# ram.net
KiCad netlist of a schematic drawn in Altium Designer
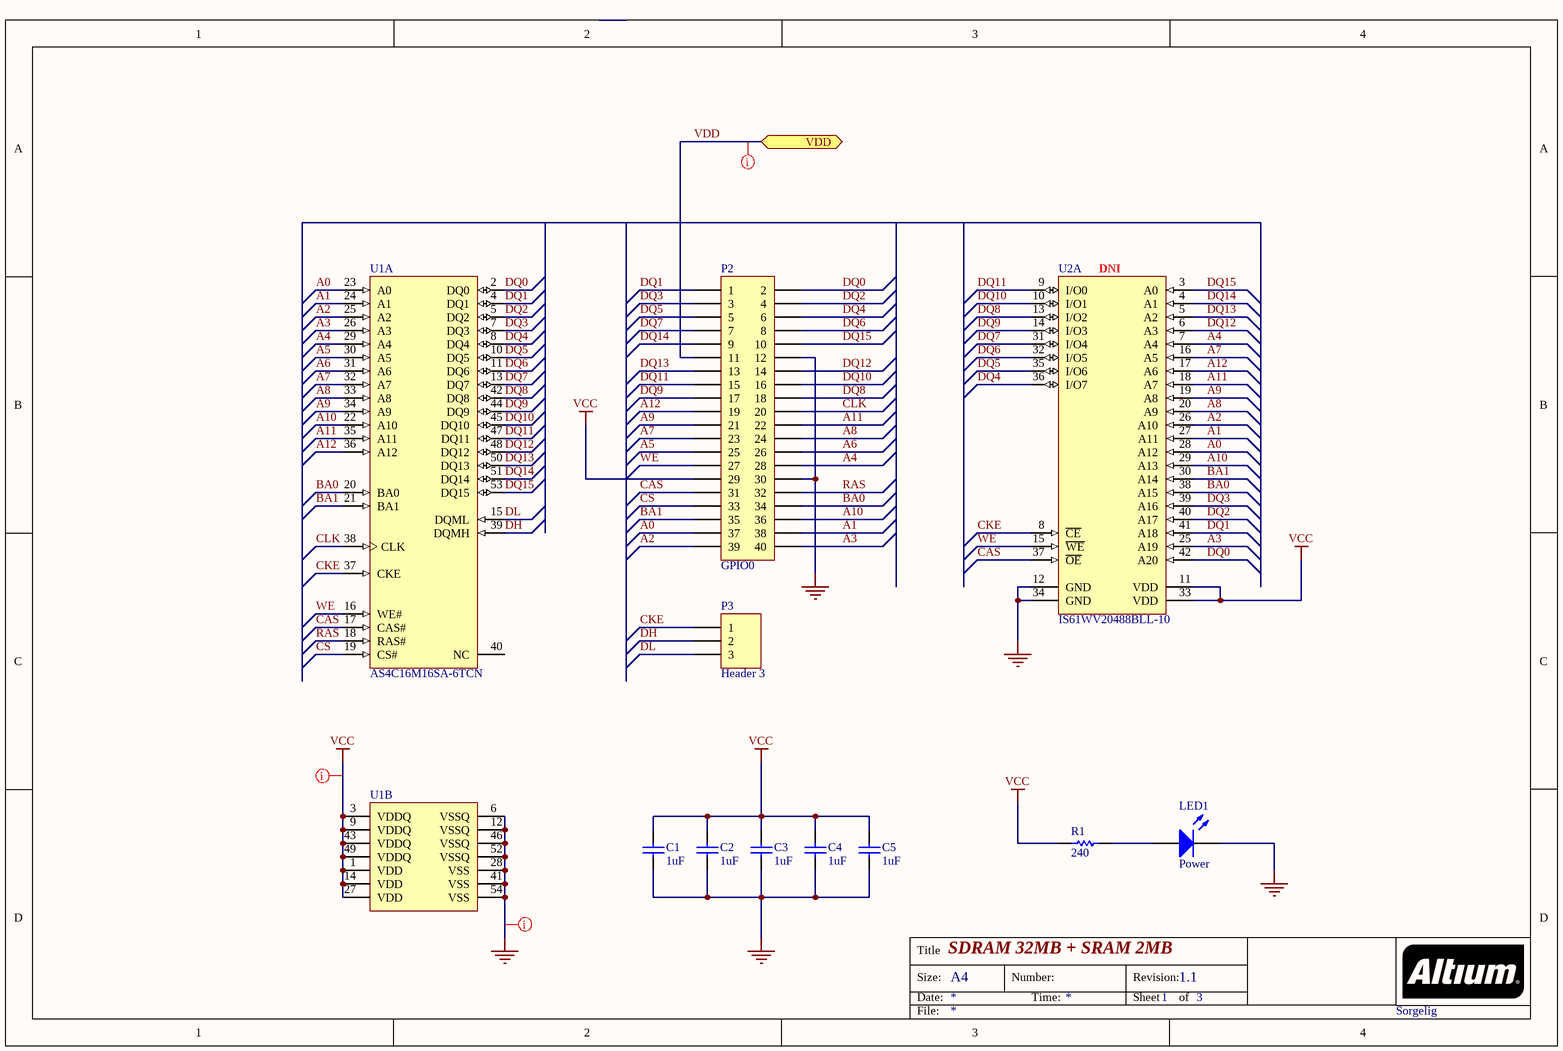
[diagram p0: ram.SchDoc]

(export (version "E")
  (design (tool "Eeschema 10.0.6"))
  (components
    (comp (ref "C1")
      (value "1uF")
      (footprint "C0805")
      (description "Ceramic Chip Capacitor - Standard")
      (fields (field (name "Comment") "C0805") (field (name "PUBLISHER") "Altium Limited"))
      (libsource (lib "lib") (part "C0805"))
    )
    (comp (ref "C2")
      (value "1uF")
      (footprint "C0805")
      (description "Ceramic Chip Capacitor - Standard")
      (fields (field (name "Comment") "C0805") (field (name "PUBLISHER") "Altium Limited"))
      (libsource (lib "lib") (part "C0805"))
    )
    (comp (ref "C3")
      (value "1uF")
      (footprint "C0805")
      (description "Ceramic Chip Capacitor - Standard")
      (fields (field (name "Comment") "+") (field (name "PUBLISHER") "Altium Limited"))
      (libsource (lib "lib") (part "C0805"))
    )
    (comp (ref "C4")
      (value "1uF")
      (footprint "C0805")
      (description "Ceramic Chip Capacitor - Standard")
      (fields (field (name "Comment") "C0805") (field (name "PUBLISHER") "Altium Limited"))
      (libsource (lib "lib") (part "C0805"))
    )
    (comp (ref "C5")
      (value "1uF")
      (footprint "C0805")
      (description "Ceramic Chip Capacitor - Standard")
      (fields (field (name "Comment") "+") (field (name "PUBLISHER") "Altium Limited"))
      (libsource (lib "lib") (part "C0805"))
    )
    (comp (ref "LED1")
      (value "Power")
      (footprint "LEDB0805")
      (description "Typical RED, GREEN, YELLOW, AMBER GaAs LED")
      (fields (field (name "PUBLISHER") "Altium Limited"))
      (libsource (lib "Miscellaneous Devices") (part "LED2"))
    )
    (comp (ref "P2")
      (value "GPIO0")
      (footprint "HDR20x2")
      (description "Header, 20-Pin, Dual row")
      (fields (field (name "PUBLISHER") "Altium Limited"))
      (libsource (lib "Miscellaneous Connectors") (part "Header 20X2"))
    )
    (comp (ref "P3")
      (value "Header 3")
      (footprint "HDR1X3")
      (description "Header, 3-Pin")
      (fields (field (name "PUBLISHER") "Altium Limited"))
      (libsource (lib "Miscellaneous Connectors") (part "Header 3"))
    )
    (comp (ref "R1")
      (value "240")
      (footprint "R0805")
      (fields (field (name "PUBLISHER") "Altium Limited"))
      (libsource (lib "lib") (part "R0805"))
    )
    (comp (ref "U1")
      (value "AS4C16M16SA-6TCN")
      (footprint "TSOP54")
      (description "256Mb SDR SDRAM, 16Mb x 16, 6ns, 3.3V, 54-Pin TSOP")
      (fields (field (name "VOLTAGE") "3.3V ") (field (name "MANUFACTURER") "Micron"))
      (libsource (lib "lib") (part "AS4C16M16SA-6TCN"))
    )
    (comp (ref "U2")
      (value "IS61WV20488BLL-10")
      (footprint "ISSI-TSOP-2-44_N")
      (description "16 M High Speed CMOS SRAM, 2 M x 8, -40 to 85 degC, 44-Pin SOP (TSOP-2-44)")
      (fields
        (field (name "MANUFACTURER") "Integrated Silicon Solution Inc (ISSI)")
        (field (name "PARTNUMBER") "IS61WV20488BLL-10TI")
      )
      (libsource (lib "lib") (part "IS61WV20488BLL-10TI"))
    )
  )
  (nets
    (net (code "1") (name "/A0") (class "Default")
      (node (ref "P2") (pin "37") (pinfunction "37_37") (pintype "passive"))
      (node (ref "U1") (pin "23") (pinfunction "A0_23") (pintype "input"))
      (node (ref "U2") (pin "28") (pinfunction "A12_28") (pintype "input"))
    )
    (net (code "2") (name "/A1") (class "Default")
      (node (ref "P2") (pin "38") (pinfunction "38_38") (pintype "passive"))
      (node (ref "U1") (pin "24") (pinfunction "A1_24") (pintype "input"))
      (node (ref "U2") (pin "27") (pinfunction "A11_27") (pintype "input"))
    )
    (net (code "3") (name "/A2") (class "Default")
      (node (ref "P2") (pin "39") (pinfunction "39_39") (pintype "passive"))
      (node (ref "U1") (pin "25") (pinfunction "A2_25") (pintype "input"))
      (node (ref "U2") (pin "26") (pinfunction "A10_26") (pintype "input"))
    )
    (net (code "4") (name "/A3") (class "Default")
      (node (ref "P2") (pin "40") (pinfunction "40_40") (pintype "passive"))
      (node (ref "U1") (pin "26") (pinfunction "A3_26") (pintype "input"))
      (node (ref "U2") (pin "25") (pinfunction "A19_25") (pintype "input"))
    )
    (net (code "5") (name "/A4") (class "Default")
      (node (ref "P2") (pin "28") (pinfunction "28_28") (pintype "passive"))
      (node (ref "U1") (pin "29") (pinfunction "A4_29") (pintype "input"))
      (node (ref "U2") (pin "7") (pinfunction "A4_7") (pintype "input"))
    )
    (net (code "6") (name "/A5") (class "Default")
      (node (ref "P2") (pin "25") (pinfunction "25_25") (pintype "passive"))
      (node (ref "U1") (pin "30") (pinfunction "A5_30") (pintype "input"))
    )
    (net (code "7") (name "/A6") (class "Default")
      (node (ref "P2") (pin "26") (pinfunction "26_26") (pintype "passive"))
      (node (ref "U1") (pin "31") (pinfunction "A6_31") (pintype "input"))
    )
    (net (code "8") (name "/A7") (class "Default")
      (node (ref "P2") (pin "23") (pinfunction "23_23") (pintype "passive"))
      (node (ref "U1") (pin "32") (pinfunction "A7_32") (pintype "input"))
      (node (ref "U2") (pin "16") (pinfunction "A5_16") (pintype "input"))
    )
    (net (code "9") (name "/A8") (class "Default")
      (node (ref "P2") (pin "24") (pinfunction "24_24") (pintype "passive"))
      (node (ref "U1") (pin "33") (pinfunction "A8_33") (pintype "input"))
      (node (ref "U2") (pin "20") (pinfunction "A9_20") (pintype "input"))
    )
    (net (code "10") (name "/A9") (class "Default")
      (node (ref "P2") (pin "21") (pinfunction "21_21") (pintype "passive"))
      (node (ref "U1") (pin "34") (pinfunction "A9_34") (pintype "input"))
      (node (ref "U2") (pin "19") (pinfunction "A8_19") (pintype "input"))
    )
    (net (code "11") (name "/A10") (class "Default")
      (node (ref "P2") (pin "36") (pinfunction "36_36") (pintype "passive"))
      (node (ref "U1") (pin "22") (pinfunction "A10_22") (pintype "input"))
      (node (ref "U2") (pin "29") (pinfunction "A13_29") (pintype "input"))
    )
    (net (code "12") (name "/A11") (class "Default")
      (node (ref "P2") (pin "22") (pinfunction "22_22") (pintype "passive"))
      (node (ref "U1") (pin "35") (pinfunction "A11_35") (pintype "input"))
      (node (ref "U2") (pin "18") (pinfunction "A7_18") (pintype "input"))
    )
    (net (code "13") (name "/A12") (class "Default")
      (node (ref "P2") (pin "19") (pinfunction "19_19") (pintype "passive"))
      (node (ref "U1") (pin "36") (pinfunction "A12_36") (pintype "input"))
      (node (ref "U2") (pin "17") (pinfunction "A6_17") (pintype "input"))
    )
    (net (code "14") (name "/BA0") (class "Default")
      (node (ref "P2") (pin "34") (pinfunction "34_34") (pintype "passive"))
      (node (ref "U1") (pin "20") (pinfunction "BA0_20") (pintype "input"))
      (node (ref "U2") (pin "38") (pinfunction "A15_38") (pintype "input"))
    )
    (net (code "15") (name "/BA1") (class "Default")
      (node (ref "P2") (pin "35") (pinfunction "35_35") (pintype "passive"))
      (node (ref "U1") (pin "21") (pinfunction "BA1_21") (pintype "input"))
      (node (ref "U2") (pin "30") (pinfunction "A14_30") (pintype "input"))
    )
    (net (code "16") (name "/CAS") (class "Default")
      (node (ref "P2") (pin "31") (pinfunction "31_31") (pintype "passive"))
      (node (ref "U1") (pin "17") (pinfunction "CAS#_17") (pintype "input"))
      (node (ref "U2") (pin "37") (pinfunction "~{OE}_37") (pintype "input"))
    )
    (net (code "17") (name "/CKE") (class "Default")
      (node (ref "P3") (pin "1") (pinfunction "1_1") (pintype "passive"))
      (node (ref "U1") (pin "37") (pinfunction "CKE_37") (pintype "input"))
      (node (ref "U2") (pin "8") (pinfunction "~{CE}_8") (pintype "input"))
    )
    (net (code "18") (name "/CLK") (class "Default")
      (node (ref "P2") (pin "20") (pinfunction "20_20") (pintype "passive"))
      (node (ref "U1") (pin "38") (pinfunction "CLK_38") (pintype "input"))
    )
    (net (code "19") (name "/CS") (class "Default")
      (node (ref "P2") (pin "33") (pinfunction "33_33") (pintype "passive"))
      (node (ref "U1") (pin "19") (pinfunction "CS#_19") (pintype "input"))
    )
    (net (code "20") (name "/DH") (class "Default")
      (node (ref "P3") (pin "2") (pinfunction "2_2") (pintype "passive"))
      (node (ref "U1") (pin "39") (pinfunction "DQMH_39") (pintype "input"))
    )
    (net (code "21") (name "/DL") (class "Default")
      (node (ref "P3") (pin "3") (pinfunction "3_3") (pintype "passive"))
      (node (ref "U1") (pin "15") (pinfunction "DQML_15") (pintype "input"))
    )
    (net (code "22") (name "/DQ0") (class "Default")
      (node (ref "P2") (pin "2") (pinfunction "2_2") (pintype "passive"))
      (node (ref "U1") (pin "2") (pinfunction "DQ0_2") (pintype "bidirectional"))
      (node (ref "U2") (pin "42") (pinfunction "A20_42") (pintype "input"))
    )
    (net (code "23") (name "/DQ1") (class "Default")
      (node (ref "P2") (pin "1") (pinfunction "1_1") (pintype "passive"))
      (node (ref "U1") (pin "4") (pinfunction "DQ1_4") (pintype "bidirectional"))
      (node (ref "U2") (pin "41") (pinfunction "A18_41") (pintype "input"))
    )
    (net (code "24") (name "/DQ2") (class "Default")
      (node (ref "P2") (pin "4") (pinfunction "4_4") (pintype "passive"))
      (node (ref "U1") (pin "5") (pinfunction "DQ2_5") (pintype "bidirectional"))
      (node (ref "U2") (pin "40") (pinfunction "A17_40") (pintype "input"))
    )
    (net (code "25") (name "/DQ3") (class "Default")
      (node (ref "P2") (pin "3") (pinfunction "3_3") (pintype "passive"))
      (node (ref "U1") (pin "7") (pinfunction "DQ3_7") (pintype "bidirectional"))
      (node (ref "U2") (pin "39") (pinfunction "A16_39") (pintype "input"))
    )
    (net (code "26") (name "/DQ4") (class "Default")
      (node (ref "P2") (pin "6") (pinfunction "6_6") (pintype "passive"))
      (node (ref "U1") (pin "8") (pinfunction "DQ4_8") (pintype "bidirectional"))
      (node (ref "U2") (pin "36") (pinfunction "I/O7_36") (pintype "bidirectional"))
    )
    (net (code "27") (name "/DQ5") (class "Default")
      (node (ref "P2") (pin "5") (pinfunction "5_5") (pintype "passive"))
      (node (ref "U1") (pin "10") (pinfunction "DQ5_10") (pintype "bidirectional"))
      (node (ref "U2") (pin "35") (pinfunction "I/O6_35") (pintype "bidirectional"))
    )
    (net (code "28") (name "/DQ6") (class "Default")
      (node (ref "P2") (pin "8") (pinfunction "8_8") (pintype "passive"))
      (node (ref "U1") (pin "11") (pinfunction "DQ6_11") (pintype "bidirectional"))
      (node (ref "U2") (pin "32") (pinfunction "I/O5_32") (pintype "bidirectional"))
    )
    (net (code "29") (name "/DQ7") (class "Default")
      (node (ref "P2") (pin "7") (pinfunction "7_7") (pintype "passive"))
      (node (ref "U1") (pin "13") (pinfunction "DQ7_13") (pintype "bidirectional"))
      (node (ref "U2") (pin "31") (pinfunction "I/O4_31") (pintype "bidirectional"))
    )
    (net (code "30") (name "/DQ8") (class "Default")
      (node (ref "P2") (pin "18") (pinfunction "18_18") (pintype "passive"))
      (node (ref "U1") (pin "42") (pinfunction "DQ8_42") (pintype "bidirectional"))
      (node (ref "U2") (pin "13") (pinfunction "I/O2_13") (pintype "bidirectional"))
    )
    (net (code "31") (name "/DQ9") (class "Default")
      (node (ref "P2") (pin "17") (pinfunction "17_17") (pintype "passive"))
      (node (ref "U1") (pin "44") (pinfunction "DQ9_44") (pintype "bidirectional"))
      (node (ref "U2") (pin "14") (pinfunction "I/O3_14") (pintype "bidirectional"))
    )
    (net (code "32") (name "/DQ10") (class "Default")
      (node (ref "P2") (pin "16") (pinfunction "16_16") (pintype "passive"))
      (node (ref "U1") (pin "45") (pinfunction "DQ10_45") (pintype "bidirectional"))
      (node (ref "U2") (pin "10") (pinfunction "I/O1_10") (pintype "bidirectional"))
    )
    (net (code "33") (name "/DQ11") (class "Default")
      (node (ref "P2") (pin "15") (pinfunction "15_15") (pintype "passive"))
      (node (ref "U1") (pin "47") (pinfunction "DQ11_47") (pintype "bidirectional"))
      (node (ref "U2") (pin "9") (pinfunction "I/O0_9") (pintype "bidirectional"))
    )
    (net (code "34") (name "/DQ12") (class "Default")
      (node (ref "P2") (pin "14") (pinfunction "14_14") (pintype "passive"))
      (node (ref "U1") (pin "48") (pinfunction "DQ12_48") (pintype "bidirectional"))
      (node (ref "U2") (pin "6") (pinfunction "A3_6") (pintype "input"))
    )
    (net (code "35") (name "/DQ13") (class "Default")
      (node (ref "P2") (pin "13") (pinfunction "13_13") (pintype "passive"))
      (node (ref "U1") (pin "50") (pinfunction "DQ13_50") (pintype "bidirectional"))
      (node (ref "U2") (pin "5") (pinfunction "A2_5") (pintype "input"))
    )
    (net (code "36") (name "/DQ14") (class "Default")
      (node (ref "P2") (pin "9") (pinfunction "9_9") (pintype "passive"))
      (node (ref "U1") (pin "51") (pinfunction "DQ14_51") (pintype "bidirectional"))
      (node (ref "U2") (pin "4") (pinfunction "A1_4") (pintype "input"))
    )
    (net (code "37") (name "/DQ15") (class "Default")
      (node (ref "P2") (pin "10") (pinfunction "10_10") (pintype "passive"))
      (node (ref "U1") (pin "53") (pinfunction "DQ15_53") (pintype "bidirectional"))
      (node (ref "U2") (pin "3") (pinfunction "A0_3") (pintype "input"))
    )
    (net (code "38") (name "/RAS") (class "Default")
      (node (ref "P2") (pin "32") (pinfunction "32_32") (pintype "passive"))
      (node (ref "U1") (pin "18") (pinfunction "RAS#_18") (pintype "input"))
    )
    (net (code "39") (name "/VDD") (class "Default")
      (node (ref "P2") (pin "11") (pinfunction "11_11") (pintype "power_in"))
    )
    (net (code "40") (name "/WE") (class "Default")
      (node (ref "P2") (pin "27") (pinfunction "27_27") (pintype "passive"))
      (node (ref "U1") (pin "16") (pinfunction "WE#_16") (pintype "input"))
      (node (ref "U2") (pin "15") (pinfunction "~{WE}_15") (pintype "input"))
    )
    (net (code "41") (name "GND") (class "Default")
      (node (ref "C1") (pin "1") (pinfunction "1_1") (pintype "passive"))
      (node (ref "C2") (pin "1") (pinfunction "1_1") (pintype "passive"))
      (node (ref "C3") (pin "1") (pinfunction "1_1") (pintype "passive"))
      (node (ref "C4") (pin "1") (pinfunction "1_1") (pintype "passive"))
      (node (ref "C5") (pin "1") (pinfunction "1_1") (pintype "passive"))
      (node (ref "LED1") (pin "2") (pinfunction "K_2") (pintype "passive"))
      (node (ref "P2") (pin "12") (pinfunction "12_12") (pintype "power_in"))
      (node (ref "P2") (pin "30") (pinfunction "30_30") (pintype "power_in"))
      (node (ref "U1") (pin "12") (pinfunction "VSSQ_12") (pintype "power_in"))
      (node (ref "U1") (pin "28") (pinfunction "VSS_28") (pintype "power_in"))
      (node (ref "U1") (pin "41") (pinfunction "VSS_41") (pintype "power_in"))
      (node (ref "U1") (pin "46") (pinfunction "VSSQ_46") (pintype "power_in"))
      (node (ref "U1") (pin "52") (pinfunction "VSSQ_52") (pintype "power_in"))
      (node (ref "U1") (pin "54") (pinfunction "VSS_54") (pintype "power_in"))
      (node (ref "U1") (pin "6") (pinfunction "VSSQ_6") (pintype "power_in"))
      (node (ref "U2") (pin "12") (pinfunction "GND_12") (pintype "power_in"))
      (node (ref "U2") (pin "34") (pinfunction "GND_34") (pintype "power_in"))
    )
    (net (code "42") (name "Net-(LED1-A)") (class "Default")
      (node (ref "LED1") (pin "1") (pinfunction "A_1") (pintype "passive"))
      (node (ref "R1") (pin "1") (pinfunction "1_1") (pintype "passive"))
    )
    (net (code "43") (name "VCC") (class "Default")
      (node (ref "C1") (pin "2") (pinfunction "2_2") (pintype "passive"))
      (node (ref "C2") (pin "2") (pinfunction "2_2") (pintype "passive"))
      (node (ref "C3") (pin "2") (pinfunction "2_2") (pintype "passive"))
      (node (ref "C4") (pin "2") (pinfunction "2_2") (pintype "passive"))
      (node (ref "C5") (pin "2") (pinfunction "2_2") (pintype "passive"))
      (node (ref "P2") (pin "29") (pinfunction "29_29") (pintype "power_in"))
      (node (ref "R1") (pin "2") (pinfunction "2_2") (pintype "passive"))
      (node (ref "U1") (pin "1") (pinfunction "VDD_1") (pintype "power_in"))
      (node (ref "U1") (pin "14") (pinfunction "VDD_14") (pintype "power_in"))
      (node (ref "U1") (pin "27") (pinfunction "VDD_27") (pintype "power_in"))
      (node (ref "U1") (pin "3") (pinfunction "VDDQ_3") (pintype "power_in"))
      (node (ref "U1") (pin "43") (pinfunction "VDDQ_43") (pintype "power_in"))
      (node (ref "U1") (pin "49") (pinfunction "VDDQ_49") (pintype "power_in"))
      (node (ref "U1") (pin "9") (pinfunction "VDDQ_9") (pintype "power_in"))
      (node (ref "U2") (pin "11") (pinfunction "VDD_11") (pintype "power_in"))
      (node (ref "U2") (pin "33") (pinfunction "VDD_33") (pintype "power_in"))
    )
    (net (code "44") (name "unconnected-(U1A-NC-Pad40)") (class "Default")
      (node (ref "U1") (pin "40") (pinfunction "NC_40") (pintype "passive"))
    )
  )
)
